# 06-LORA.net
KiCad netlist of a schematic drawn in Altium Designer
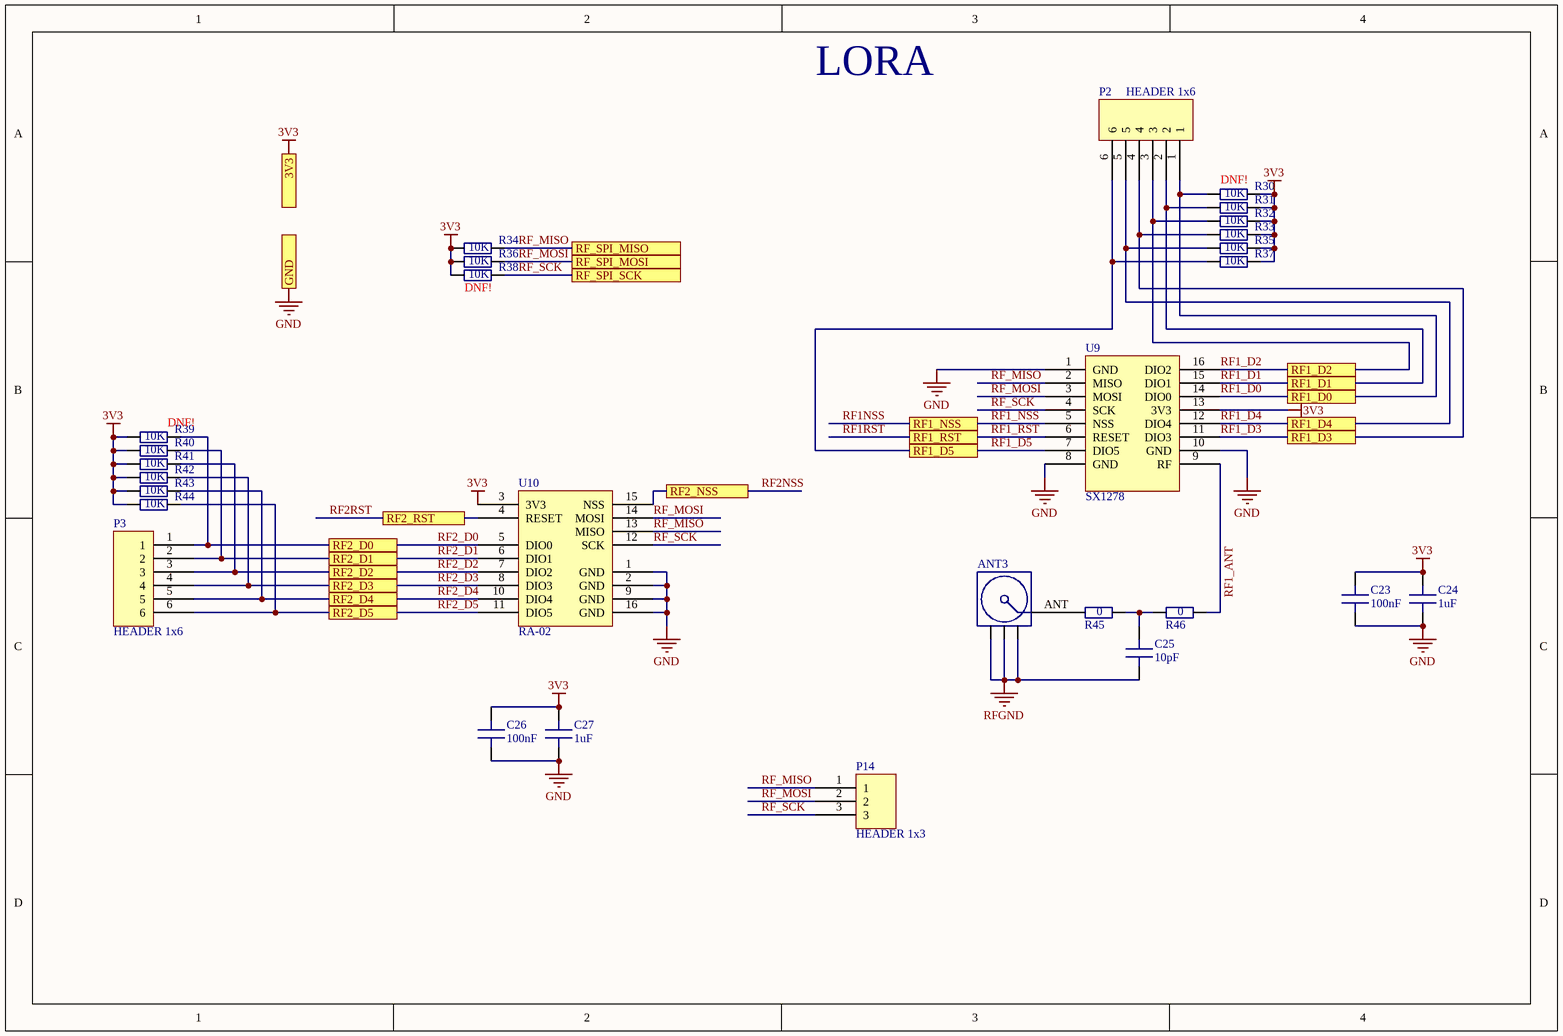
[diagram p0: 06-LORA.SchDoc]

(export (version "E")
  (design (tool "Eeschema 10.0.6"))
  (components
    (comp (ref "ANT3")
      (value "UFL")
      (footprint "U.FL CONNECTOR")
      (description "Generic U.FL connector with 1 ANT + 3 GND")
      (libsource (lib "ComponentsLib") (part "ANT-U.FL"))
    )
    (comp (ref "C23")
      (value "100nF")
      (footprint "C0603")
      (description "Ceramic capacitor")
      (fields (field (name "VOLTAGE") "16V"))
      (libsource (lib "A.Shelestov_Capacitors") (part "C0603_100nF_16V"))
    )
    (comp (ref "C24")
      (value "1uF")
      (footprint "C0805")
      (description "Ceramic capacitor")
      (fields (field (name "VOLTAGE") "25V"))
      (libsource (lib "A.Shelestov_Capacitors") (part "C0805_1uF_25V"))
    )
    (comp (ref "C25")
      (value "10pF")
      (footprint "C0402")
      (description "Ceramic capacitor")
      (fields (field (name "VOLTAGE") "50V"))
      (libsource (lib "A.Shelestov_Capacitors") (part "C0402_10pF_50V"))
    )
    (comp (ref "C26")
      (value "100nF")
      (footprint "C0603")
      (description "Ceramic capacitor")
      (fields (field (name "VOLTAGE") "16V"))
      (libsource (lib "A.Shelestov_Capacitors") (part "C0603_100nF_16V"))
    )
    (comp (ref "C27")
      (value "1uF")
      (footprint "C0805")
      (description "Ceramic capacitor")
      (fields (field (name "VOLTAGE") "25V"))
      (libsource (lib "A.Shelestov_Capacitors") (part "C0805_1uF_25V"))
    )
    (comp (ref "P2")
      (value "HEADER 1x6")
      (footprint "HEADER 1x6 2.54")
      (libsource (lib "") (part "HEADER 1x6_1"))
    )
    (comp (ref "P3")
      (value "HEADER 1x6")
      (footprint "HEADER 1x6 2.54")
      (libsource (lib "ComponentsLib") (part "HEADER 1x6"))
    )
    (comp (ref "P14")
      (value "HEADER 1x3")
      (footprint "UART_2.54")
      (libsource (lib "ComponentsLib") (part "HEADER 1x3"))
    )
    (comp (ref "R30")
      (value "~")
      (footprint "R0603")
      (description "Resistor General")
      (fields (field (name "TOLERANCE") "5%") (field (name "RESISTANCE") "10K"))
      (libsource (lib "A.Shelestov_Resistors") (part "R0603_10K"))
    )
    (comp (ref "R31")
      (value "~")
      (footprint "R0603")
      (description "Resistor General")
      (fields (field (name "TOLERANCE") "5%") (field (name "RESISTANCE") "10K"))
      (libsource (lib "A.Shelestov_Resistors") (part "R0603_10K"))
    )
    (comp (ref "R32")
      (value "~")
      (footprint "R0603")
      (description "Resistor General")
      (fields (field (name "TOLERANCE") "5%") (field (name "RESISTANCE") "10K"))
      (libsource (lib "A.Shelestov_Resistors") (part "R0603_10K"))
    )
    (comp (ref "R33")
      (value "~")
      (footprint "R0603")
      (description "Resistor General")
      (fields (field (name "TOLERANCE") "5%") (field (name "RESISTANCE") "10K"))
      (libsource (lib "A.Shelestov_Resistors") (part "R0603_10K"))
    )
    (comp (ref "R34")
      (value "~")
      (footprint "R0603")
      (description "Resistor General")
      (fields (field (name "TOLERANCE") "5%") (field (name "RESISTANCE") "10K"))
      (libsource (lib "A.Shelestov_Resistors") (part "R0603_10K"))
    )
    (comp (ref "R35")
      (value "~")
      (footprint "R0603")
      (description "Resistor General")
      (fields (field (name "TOLERANCE") "5%") (field (name "RESISTANCE") "10K"))
      (libsource (lib "A.Shelestov_Resistors") (part "R0603_10K"))
    )
    (comp (ref "R36")
      (value "~")
      (footprint "R0603")
      (description "Resistor General")
      (fields (field (name "TOLERANCE") "5%") (field (name "RESISTANCE") "10K"))
      (libsource (lib "A.Shelestov_Resistors") (part "R0603_10K"))
    )
    (comp (ref "R37")
      (value "~")
      (footprint "R0603")
      (description "Resistor General")
      (fields (field (name "TOLERANCE") "5%") (field (name "RESISTANCE") "10K"))
      (libsource (lib "A.Shelestov_Resistors") (part "R0603_10K"))
    )
    (comp (ref "R38")
      (value "~")
      (footprint "R0603")
      (description "Resistor General")
      (fields (field (name "TOLERANCE") "5%") (field (name "RESISTANCE") "10K"))
      (libsource (lib "A.Shelestov_Resistors") (part "R0603_10K"))
    )
    (comp (ref "R39")
      (value "~")
      (footprint "R0603")
      (description "Resistor General")
      (fields (field (name "TOLERANCE") "5%") (field (name "RESISTANCE") "10K"))
      (libsource (lib "A.Shelestov_Resistors") (part "R0603_10K"))
    )
    (comp (ref "R40")
      (value "~")
      (footprint "R0603")
      (description "Resistor General")
      (fields (field (name "TOLERANCE") "5%") (field (name "RESISTANCE") "10K"))
      (libsource (lib "A.Shelestov_Resistors") (part "R0603_10K"))
    )
    (comp (ref "R41")
      (value "~")
      (footprint "R0603")
      (description "Resistor General")
      (fields (field (name "TOLERANCE") "5%") (field (name "RESISTANCE") "10K"))
      (libsource (lib "A.Shelestov_Resistors") (part "R0603_10K"))
    )
    (comp (ref "R42")
      (value "~")
      (footprint "R0603")
      (description "Resistor General")
      (fields (field (name "TOLERANCE") "5%") (field (name "RESISTANCE") "10K"))
      (libsource (lib "A.Shelestov_Resistors") (part "R0603_10K"))
    )
    (comp (ref "R43")
      (value "~")
      (footprint "R0603")
      (description "Resistor General")
      (fields (field (name "TOLERANCE") "5%") (field (name "RESISTANCE") "10K"))
      (libsource (lib "A.Shelestov_Resistors") (part "R0603_10K"))
    )
    (comp (ref "R44")
      (value "~")
      (footprint "R0603")
      (description "Resistor General")
      (fields (field (name "TOLERANCE") "5%") (field (name "RESISTANCE") "10K"))
      (libsource (lib "A.Shelestov_Resistors") (part "R0603_10K"))
    )
    (comp (ref "R45")
      (value "~")
      (footprint "R0402")
      (description "Resistor General")
      (fields (field (name "RESISTANCE") "0"))
      (libsource (lib "A.Shelestov_Resistors") (part "R0402_0R"))
    )
    (comp (ref "R46")
      (value "~")
      (footprint "R0402")
      (description "Resistor General")
      (fields (field (name "RESISTANCE") "0"))
      (libsource (lib "A.Shelestov_Resistors") (part "R0402_0R"))
    )
    (comp (ref "U9")
      (value "SX1278")
      (footprint "SX1278")
      (description "SX1278 LoRa modem")
      (libsource (lib "ComponentsLib") (part "SX1278"))
    )
    (comp (ref "U10")
      (value "RA-02")
      (footprint "RA-02")
      (description "RA-02 LoRa modem by Ai-Thinker")
      (libsource (lib "ComponentsLib") (part "RA-02"))
    )
  )
  (nets
    (net (code "1") (name "/RF1NSS") (class "Default")
      (node (ref "U9") (pin "5") (pinfunction "NSS_5") (pintype "passive"))
    )
    (net (code "2") (name "/RF1RST") (class "Default")
      (node (ref "U9") (pin "6") (pinfunction "RESET_6") (pintype "passive"))
    )
    (net (code "3") (name "/RF1_ANT") (class "Default")
      (node (ref "R46") (pin "2") (pinfunction "2_2") (pintype "passive"))
      (node (ref "U9") (pin "9") (pinfunction "RF_9") (pintype "passive"))
    )
    (net (code "4") (name "/RF1_D0") (class "Default")
      (node (ref "P2") (pin "1") (pinfunction "1_1") (pintype "passive"))
      (node (ref "R30") (pin "1") (pinfunction "1_1") (pintype "passive"))
      (node (ref "U9") (pin "14") (pinfunction "DIO0_14") (pintype "passive"))
    )
    (net (code "5") (name "/RF1_D1") (class "Default")
      (node (ref "P2") (pin "2") (pinfunction "2_2") (pintype "passive"))
      (node (ref "R31") (pin "1") (pinfunction "1_1") (pintype "passive"))
      (node (ref "U9") (pin "15") (pinfunction "DIO1_15") (pintype "passive"))
    )
    (net (code "6") (name "/RF1_D2") (class "Default")
      (node (ref "P2") (pin "3") (pinfunction "3_3") (pintype "passive"))
      (node (ref "R32") (pin "1") (pinfunction "1_1") (pintype "passive"))
      (node (ref "U9") (pin "16") (pinfunction "DIO2_16") (pintype "passive"))
    )
    (net (code "7") (name "/RF1_D3") (class "Default")
      (node (ref "P2") (pin "4") (pinfunction "4_4") (pintype "passive"))
      (node (ref "R33") (pin "1") (pinfunction "1_1") (pintype "passive"))
      (node (ref "U9") (pin "11") (pinfunction "DIO3_11") (pintype "passive"))
    )
    (net (code "8") (name "/RF1_D4") (class "Default")
      (node (ref "P2") (pin "5") (pinfunction "5_5") (pintype "passive"))
      (node (ref "R35") (pin "1") (pinfunction "1_1") (pintype "passive"))
      (node (ref "U9") (pin "12") (pinfunction "DIO4_12") (pintype "passive"))
    )
    (net (code "9") (name "/RF1_D5") (class "Default")
      (node (ref "P2") (pin "6") (pinfunction "6_6") (pintype "passive"))
      (node (ref "R37") (pin "1") (pinfunction "1_1") (pintype "passive"))
      (node (ref "U9") (pin "7") (pinfunction "DIO5_7") (pintype "passive"))
    )
    (net (code "10") (name "/RF2NSS") (class "Default")
      (node (ref "U10") (pin "15") (pinfunction "NSS_15") (pintype "passive"))
    )
    (net (code "11") (name "/RF2RST") (class "Default")
      (node (ref "U10") (pin "4") (pinfunction "RESET_4") (pintype "passive"))
    )
    (net (code "12") (name "/RF2_D0") (class "Default")
      (node (ref "P3") (pin "1") (pinfunction "1_1") (pintype "passive"))
      (node (ref "R39") (pin "2") (pinfunction "2_2") (pintype "passive"))
      (node (ref "U10") (pin "5") (pinfunction "DIO0_5") (pintype "passive"))
    )
    (net (code "13") (name "/RF2_D1") (class "Default")
      (node (ref "P3") (pin "2") (pinfunction "2_2") (pintype "passive"))
      (node (ref "R40") (pin "2") (pinfunction "2_2") (pintype "passive"))
      (node (ref "U10") (pin "6") (pinfunction "DIO1_6") (pintype "passive"))
    )
    (net (code "14") (name "/RF2_D2") (class "Default")
      (node (ref "P3") (pin "3") (pinfunction "3_3") (pintype "passive"))
      (node (ref "R41") (pin "2") (pinfunction "2_2") (pintype "passive"))
      (node (ref "U10") (pin "7") (pinfunction "DIO2_7") (pintype "passive"))
    )
    (net (code "15") (name "/RF2_D3") (class "Default")
      (node (ref "P3") (pin "4") (pinfunction "4_4") (pintype "passive"))
      (node (ref "R42") (pin "2") (pinfunction "2_2") (pintype "passive"))
      (node (ref "U10") (pin "8") (pinfunction "DIO3_8") (pintype "passive"))
    )
    (net (code "16") (name "/RF2_D4") (class "Default")
      (node (ref "P3") (pin "5") (pinfunction "5_5") (pintype "passive"))
      (node (ref "R43") (pin "2") (pinfunction "2_2") (pintype "passive"))
      (node (ref "U10") (pin "10") (pinfunction "DIO4_10") (pintype "passive"))
    )
    (net (code "17") (name "/RF2_D5") (class "Default")
      (node (ref "P3") (pin "6") (pinfunction "6_6") (pintype "passive"))
      (node (ref "R44") (pin "2") (pinfunction "2_2") (pintype "passive"))
      (node (ref "U10") (pin "11") (pinfunction "DIO5_11") (pintype "passive"))
    )
    (net (code "18") (name "/RF_MISO") (class "Default")
      (node (ref "P14") (pin "1") (pinfunction "1_1") (pintype "passive"))
      (node (ref "R34") (pin "2") (pinfunction "2_2") (pintype "passive"))
      (node (ref "U10") (pin "13") (pinfunction "MISO_13") (pintype "passive"))
      (node (ref "U9") (pin "2") (pinfunction "MISO_2") (pintype "passive"))
    )
    (net (code "19") (name "/RF_MOSI") (class "Default")
      (node (ref "P14") (pin "2") (pinfunction "2_2") (pintype "passive"))
      (node (ref "R36") (pin "2") (pinfunction "2_2") (pintype "passive"))
      (node (ref "U10") (pin "14") (pinfunction "MOSI_14") (pintype "passive"))
      (node (ref "U9") (pin "3") (pinfunction "MOSI_3") (pintype "passive"))
    )
    (net (code "20") (name "/RF_SCK") (class "Default")
      (node (ref "P14") (pin "3") (pinfunction "3_3") (pintype "passive"))
      (node (ref "R38") (pin "2") (pinfunction "2_2") (pintype "passive"))
      (node (ref "U10") (pin "12") (pinfunction "SCK_12") (pintype "passive"))
      (node (ref "U9") (pin "4") (pinfunction "SCK_4") (pintype "passive"))
    )
    (net (code "21") (name "3V3") (class "Default")
      (node (ref "C23") (pin "2") (pinfunction "2_2") (pintype "passive"))
      (node (ref "C24") (pin "2") (pinfunction "2_2") (pintype "passive"))
      (node (ref "C26") (pin "2") (pinfunction "2_2") (pintype "passive"))
      (node (ref "C27") (pin "2") (pinfunction "2_2") (pintype "passive"))
      (node (ref "R30") (pin "2") (pinfunction "2_2") (pintype "passive"))
      (node (ref "R31") (pin "2") (pinfunction "2_2") (pintype "passive"))
      (node (ref "R32") (pin "2") (pinfunction "2_2") (pintype "passive"))
      (node (ref "R33") (pin "2") (pinfunction "2_2") (pintype "passive"))
      (node (ref "R34") (pin "1") (pinfunction "1_1") (pintype "passive"))
      (node (ref "R35") (pin "2") (pinfunction "2_2") (pintype "passive"))
      (node (ref "R36") (pin "1") (pinfunction "1_1") (pintype "passive"))
      (node (ref "R37") (pin "2") (pinfunction "2_2") (pintype "passive"))
      (node (ref "R38") (pin "1") (pinfunction "1_1") (pintype "passive"))
      (node (ref "R39") (pin "1") (pinfunction "1_1") (pintype "passive"))
      (node (ref "R40") (pin "1") (pinfunction "1_1") (pintype "passive"))
      (node (ref "R41") (pin "1") (pinfunction "1_1") (pintype "passive"))
      (node (ref "R42") (pin "1") (pinfunction "1_1") (pintype "passive"))
      (node (ref "R43") (pin "1") (pinfunction "1_1") (pintype "passive"))
      (node (ref "R44") (pin "1") (pinfunction "1_1") (pintype "passive"))
      (node (ref "U10") (pin "3") (pinfunction "3V3_3") (pintype "passive"))
      (node (ref "U9") (pin "13") (pinfunction "3V3_13") (pintype "passive"))
    )
    (net (code "22") (name "GND") (class "Default")
      (node (ref "C23") (pin "1") (pinfunction "1_1") (pintype "passive"))
      (node (ref "C24") (pin "1") (pinfunction "1_1") (pintype "passive"))
      (node (ref "C26") (pin "1") (pinfunction "1_1") (pintype "passive"))
      (node (ref "C27") (pin "1") (pinfunction "1_1") (pintype "passive"))
      (node (ref "U10") (pin "1") (pinfunction "GND_1") (pintype "passive"))
      (node (ref "U10") (pin "16") (pinfunction "GND_16") (pintype "passive"))
      (node (ref "U10") (pin "2") (pinfunction "GND_2") (pintype "passive"))
      (node (ref "U10") (pin "9") (pinfunction "GND_9") (pintype "passive"))
      (node (ref "U9") (pin "1") (pinfunction "GND_1") (pintype "passive"))
      (node (ref "U9") (pin "10") (pinfunction "GND_10") (pintype "passive"))
      (node (ref "U9") (pin "8") (pinfunction "GND_8") (pintype "passive"))
    )
    (net (code "23") (name "Net-(ANT3-SIGNAL)") (class "Default")
      (node (ref "ANT3") (pin "ANT") (pinfunction "SIGNAL_ANT") (pintype "passive"))
      (node (ref "R45") (pin "1") (pinfunction "1_1") (pintype "passive"))
    )
    (net (code "24") (name "Net-(C25-Pad2)") (class "Default")
      (node (ref "C25") (pin "2") (pinfunction "2_2") (pintype "passive"))
      (node (ref "R45") (pin "2") (pinfunction "2_2") (pintype "passive"))
      (node (ref "R46") (pin "1") (pinfunction "1_1") (pintype "passive"))
    )
    (net (code "25") (name "RFGND") (class "Default")
      (node (ref "ANT3") (pin "GND") (pinfunction "GND_GND") (pintype "passive"))
      (node (ref "C25") (pin "1") (pinfunction "1_1") (pintype "passive"))
    )
  )
)
